# ARRAY-5050.net
KiCad netlist of a schematic drawn in Altium Designer
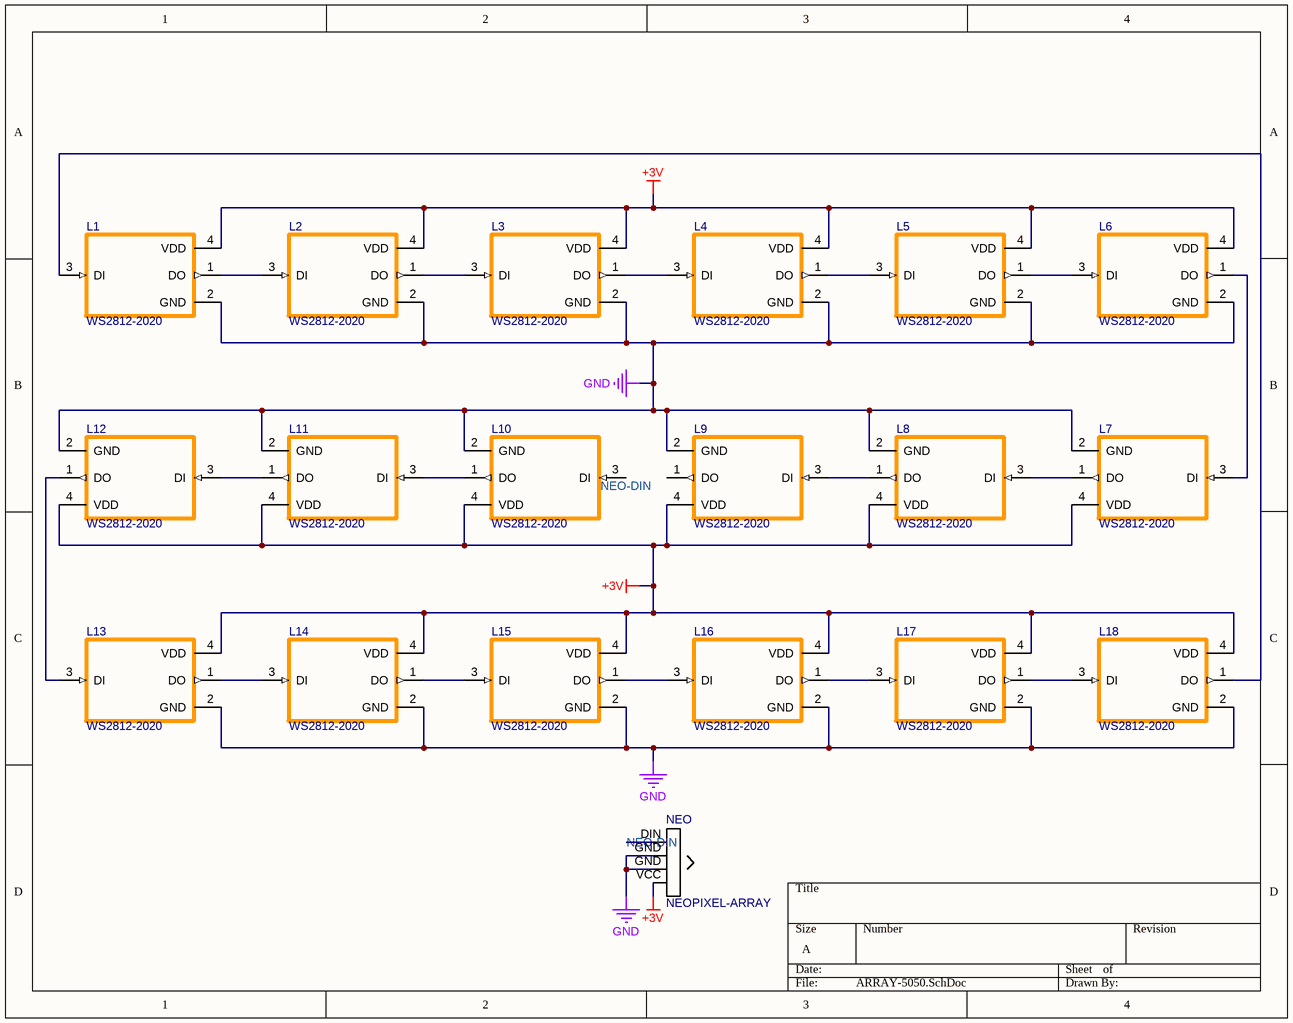
[diagram p0: ARRAY-5050.SchDoc]

(export (version "E")
  (design (tool "Eeschema 10.0.6"))
  (components
    (comp (ref "L1")
      (value "WS2812-2020")
      (footprint "NEOPIXEL-5050")
      (libsource (lib "RC") (part "NEOPIXEL-5050"))
    )
    (comp (ref "L2")
      (value "WS2812-2020")
      (footprint "NEOPIXEL-5050")
      (libsource (lib "RC") (part "NEOPIXEL-5050"))
    )
    (comp (ref "L3")
      (value "WS2812-2020")
      (footprint "NEOPIXEL-5050")
      (libsource (lib "RC") (part "NEOPIXEL-5050"))
    )
    (comp (ref "L4")
      (value "WS2812-2020")
      (footprint "NEOPIXEL-5050")
      (libsource (lib "RC") (part "NEOPIXEL-5050"))
    )
    (comp (ref "L5")
      (value "WS2812-2020")
      (footprint "NEOPIXEL-5050")
      (libsource (lib "RC") (part "NEOPIXEL-5050"))
    )
    (comp (ref "L6")
      (value "WS2812-2020")
      (footprint "NEOPIXEL-5050")
      (libsource (lib "RC") (part "NEOPIXEL-5050"))
    )
    (comp (ref "L7")
      (value "WS2812-2020")
      (footprint "NEOPIXEL-5050")
      (libsource (lib "") (part "NEOPIXEL-5050_1"))
    )
    (comp (ref "L8")
      (value "WS2812-2020")
      (footprint "NEOPIXEL-5050")
      (libsource (lib "") (part "NEOPIXEL-5050_1"))
    )
    (comp (ref "L9")
      (value "WS2812-2020")
      (footprint "NEOPIXEL-5050")
      (libsource (lib "") (part "NEOPIXEL-5050_1"))
    )
    (comp (ref "L10")
      (value "WS2812-2020")
      (footprint "NEOPIXEL-5050")
      (libsource (lib "") (part "NEOPIXEL-5050_1"))
    )
    (comp (ref "L11")
      (value "WS2812-2020")
      (footprint "NEOPIXEL-5050")
      (libsource (lib "") (part "NEOPIXEL-5050_1"))
    )
    (comp (ref "L12")
      (value "WS2812-2020")
      (footprint "NEOPIXEL-5050")
      (libsource (lib "") (part "NEOPIXEL-5050_1"))
    )
    (comp (ref "L13")
      (value "WS2812-2020")
      (footprint "NEOPIXEL-5050")
      (libsource (lib "RC") (part "NEOPIXEL-5050"))
    )
    (comp (ref "L14")
      (value "WS2812-2020")
      (footprint "NEOPIXEL-5050")
      (libsource (lib "RC") (part "NEOPIXEL-5050"))
    )
    (comp (ref "L15")
      (value "WS2812-2020")
      (footprint "NEOPIXEL-5050")
      (libsource (lib "RC") (part "NEOPIXEL-5050"))
    )
    (comp (ref "L16")
      (value "WS2812-2020")
      (footprint "NEOPIXEL-5050")
      (libsource (lib "RC") (part "NEOPIXEL-5050"))
    )
    (comp (ref "L17")
      (value "WS2812-2020")
      (footprint "NEOPIXEL-5050")
      (libsource (lib "RC") (part "NEOPIXEL-5050"))
    )
    (comp (ref "L18")
      (value "WS2812-2020")
      (footprint "NEOPIXEL-5050")
      (libsource (lib "RC") (part "NEOPIXEL-5050"))
    )
    (comp (ref "NEO")
      (value "NEOPIXEL-ARRAY")
      (footprint "NEOPIXEL-ARRAY")
      (libsource (lib "GenericRC") (part "NEOPIXEL-ARRAY"))
    )
  )
  (nets
    (net (code "1") (name "+3V") (class "Default")
      (node (ref "L1") (pin "4") (pinfunction "VDD_4") (pintype "power_in"))
      (node (ref "L10") (pin "4") (pinfunction "VDD_4") (pintype "power_in"))
      (node (ref "L11") (pin "4") (pinfunction "VDD_4") (pintype "power_in"))
      (node (ref "L12") (pin "4") (pinfunction "VDD_4") (pintype "power_in"))
      (node (ref "L13") (pin "4") (pinfunction "VDD_4") (pintype "power_in"))
      (node (ref "L14") (pin "4") (pinfunction "VDD_4") (pintype "power_in"))
      (node (ref "L15") (pin "4") (pinfunction "VDD_4") (pintype "power_in"))
      (node (ref "L16") (pin "4") (pinfunction "VDD_4") (pintype "power_in"))
      (node (ref "L17") (pin "4") (pinfunction "VDD_4") (pintype "power_in"))
      (node (ref "L18") (pin "4") (pinfunction "VDD_4") (pintype "power_in"))
      (node (ref "L2") (pin "4") (pinfunction "VDD_4") (pintype "power_in"))
      (node (ref "L3") (pin "4") (pinfunction "VDD_4") (pintype "power_in"))
      (node (ref "L4") (pin "4") (pinfunction "VDD_4") (pintype "power_in"))
      (node (ref "L5") (pin "4") (pinfunction "VDD_4") (pintype "power_in"))
      (node (ref "L6") (pin "4") (pinfunction "VDD_4") (pintype "power_in"))
      (node (ref "L7") (pin "4") (pinfunction "VDD_4") (pintype "power_in"))
      (node (ref "L8") (pin "4") (pinfunction "VDD_4") (pintype "power_in"))
      (node (ref "L9") (pin "4") (pinfunction "VDD_4") (pintype "power_in"))
      (node (ref "NEO") (pin "VCC") (pintype "passive"))
    )
    (net (code "2") (name "/NEO-DIN") (class "Default")
      (node (ref "L10") (pin "3") (pinfunction "DI_3") (pintype "input"))
      (node (ref "NEO") (pin "DIN") (pintype "passive"))
    )
    (net (code "3") (name "GND") (class "Default")
      (node (ref "L1") (pin "2") (pinfunction "GND_2") (pintype "power_in"))
      (node (ref "L10") (pin "2") (pinfunction "GND_2") (pintype "power_in"))
      (node (ref "L11") (pin "2") (pinfunction "GND_2") (pintype "power_in"))
      (node (ref "L12") (pin "2") (pinfunction "GND_2") (pintype "power_in"))
      (node (ref "L13") (pin "2") (pinfunction "GND_2") (pintype "power_in"))
      (node (ref "L14") (pin "2") (pinfunction "GND_2") (pintype "power_in"))
      (node (ref "L15") (pin "2") (pinfunction "GND_2") (pintype "power_in"))
      (node (ref "L16") (pin "2") (pinfunction "GND_2") (pintype "power_in"))
      (node (ref "L17") (pin "2") (pinfunction "GND_2") (pintype "power_in"))
      (node (ref "L18") (pin "2") (pinfunction "GND_2") (pintype "power_in"))
      (node (ref "L2") (pin "2") (pinfunction "GND_2") (pintype "power_in"))
      (node (ref "L3") (pin "2") (pinfunction "GND_2") (pintype "power_in"))
      (node (ref "L4") (pin "2") (pinfunction "GND_2") (pintype "power_in"))
      (node (ref "L5") (pin "2") (pinfunction "GND_2") (pintype "power_in"))
      (node (ref "L6") (pin "2") (pinfunction "GND_2") (pintype "power_in"))
      (node (ref "L7") (pin "2") (pinfunction "GND_2") (pintype "power_in"))
      (node (ref "L8") (pin "2") (pinfunction "GND_2") (pintype "power_in"))
      (node (ref "L9") (pin "2") (pinfunction "GND_2") (pintype "power_in"))
      (node (ref "NEO") (pin "GND") (pintype "passive"))
    )
    (net (code "4") (name "Net-(L1-DI)") (class "Default")
      (node (ref "L1") (pin "3") (pinfunction "DI_3") (pintype "input"))
      (node (ref "L18") (pin "1") (pinfunction "DO_1") (pintype "output"))
    )
    (net (code "5") (name "Net-(L1-DO)") (class "Default")
      (node (ref "L1") (pin "1") (pinfunction "DO_1") (pintype "output"))
      (node (ref "L2") (pin "3") (pinfunction "DI_3") (pintype "input"))
    )
    (net (code "6") (name "Net-(L2-DO)") (class "Default")
      (node (ref "L2") (pin "1") (pinfunction "DO_1") (pintype "output"))
      (node (ref "L3") (pin "3") (pinfunction "DI_3") (pintype "input"))
    )
    (net (code "7") (name "Net-(L3-DO)") (class "Default")
      (node (ref "L3") (pin "1") (pinfunction "DO_1") (pintype "output"))
      (node (ref "L4") (pin "3") (pinfunction "DI_3") (pintype "input"))
    )
    (net (code "8") (name "Net-(L4-DO)") (class "Default")
      (node (ref "L4") (pin "1") (pinfunction "DO_1") (pintype "output"))
      (node (ref "L5") (pin "3") (pinfunction "DI_3") (pintype "input"))
    )
    (net (code "9") (name "Net-(L5-DO)") (class "Default")
      (node (ref "L5") (pin "1") (pinfunction "DO_1") (pintype "output"))
      (node (ref "L6") (pin "3") (pinfunction "DI_3") (pintype "input"))
    )
    (net (code "10") (name "Net-(L6-DO)") (class "Default")
      (node (ref "L6") (pin "1") (pinfunction "DO_1") (pintype "output"))
      (node (ref "L7") (pin "3") (pinfunction "DI_3") (pintype "input"))
    )
    (net (code "11") (name "Net-(L7-DO)") (class "Default")
      (node (ref "L7") (pin "1") (pinfunction "DO_1") (pintype "output"))
      (node (ref "L8") (pin "3") (pinfunction "DI_3") (pintype "input"))
    )
    (net (code "12") (name "Net-(L8-DO)") (class "Default")
      (node (ref "L8") (pin "1") (pinfunction "DO_1") (pintype "output"))
      (node (ref "L9") (pin "3") (pinfunction "DI_3") (pintype "input"))
    )
    (net (code "13") (name "Net-(L10-DO)") (class "Default")
      (node (ref "L10") (pin "1") (pinfunction "DO_1") (pintype "output"))
      (node (ref "L11") (pin "3") (pinfunction "DI_3") (pintype "input"))
    )
    (net (code "14") (name "Net-(L11-DO)") (class "Default")
      (node (ref "L11") (pin "1") (pinfunction "DO_1") (pintype "output"))
      (node (ref "L12") (pin "3") (pinfunction "DI_3") (pintype "input"))
    )
    (net (code "15") (name "Net-(L12-DO)") (class "Default")
      (node (ref "L12") (pin "1") (pinfunction "DO_1") (pintype "output"))
      (node (ref "L13") (pin "3") (pinfunction "DI_3") (pintype "input"))
    )
    (net (code "16") (name "Net-(L13-DO)") (class "Default")
      (node (ref "L13") (pin "1") (pinfunction "DO_1") (pintype "output"))
      (node (ref "L14") (pin "3") (pinfunction "DI_3") (pintype "input"))
    )
    (net (code "17") (name "Net-(L14-DO)") (class "Default")
      (node (ref "L14") (pin "1") (pinfunction "DO_1") (pintype "output"))
      (node (ref "L15") (pin "3") (pinfunction "DI_3") (pintype "input"))
    )
    (net (code "18") (name "Net-(L15-DO)") (class "Default")
      (node (ref "L15") (pin "1") (pinfunction "DO_1") (pintype "output"))
      (node (ref "L16") (pin "3") (pinfunction "DI_3") (pintype "input"))
    )
    (net (code "19") (name "Net-(L16-DO)") (class "Default")
      (node (ref "L16") (pin "1") (pinfunction "DO_1") (pintype "output"))
      (node (ref "L17") (pin "3") (pinfunction "DI_3") (pintype "input"))
    )
    (net (code "20") (name "Net-(L17-DO)") (class "Default")
      (node (ref "L17") (pin "1") (pinfunction "DO_1") (pintype "output"))
      (node (ref "L18") (pin "3") (pinfunction "DI_3") (pintype "input"))
    )
    (net (code "21") (name "unconnected-(L9-DO-Pad1)") (class "Default")
      (node (ref "L9") (pin "1") (pinfunction "DO_1") (pintype "output"))
    )
  )
)
